# C210_0002_NORA_Module_220601.net
KiCad netlist of a schematic drawn in Altium Designer
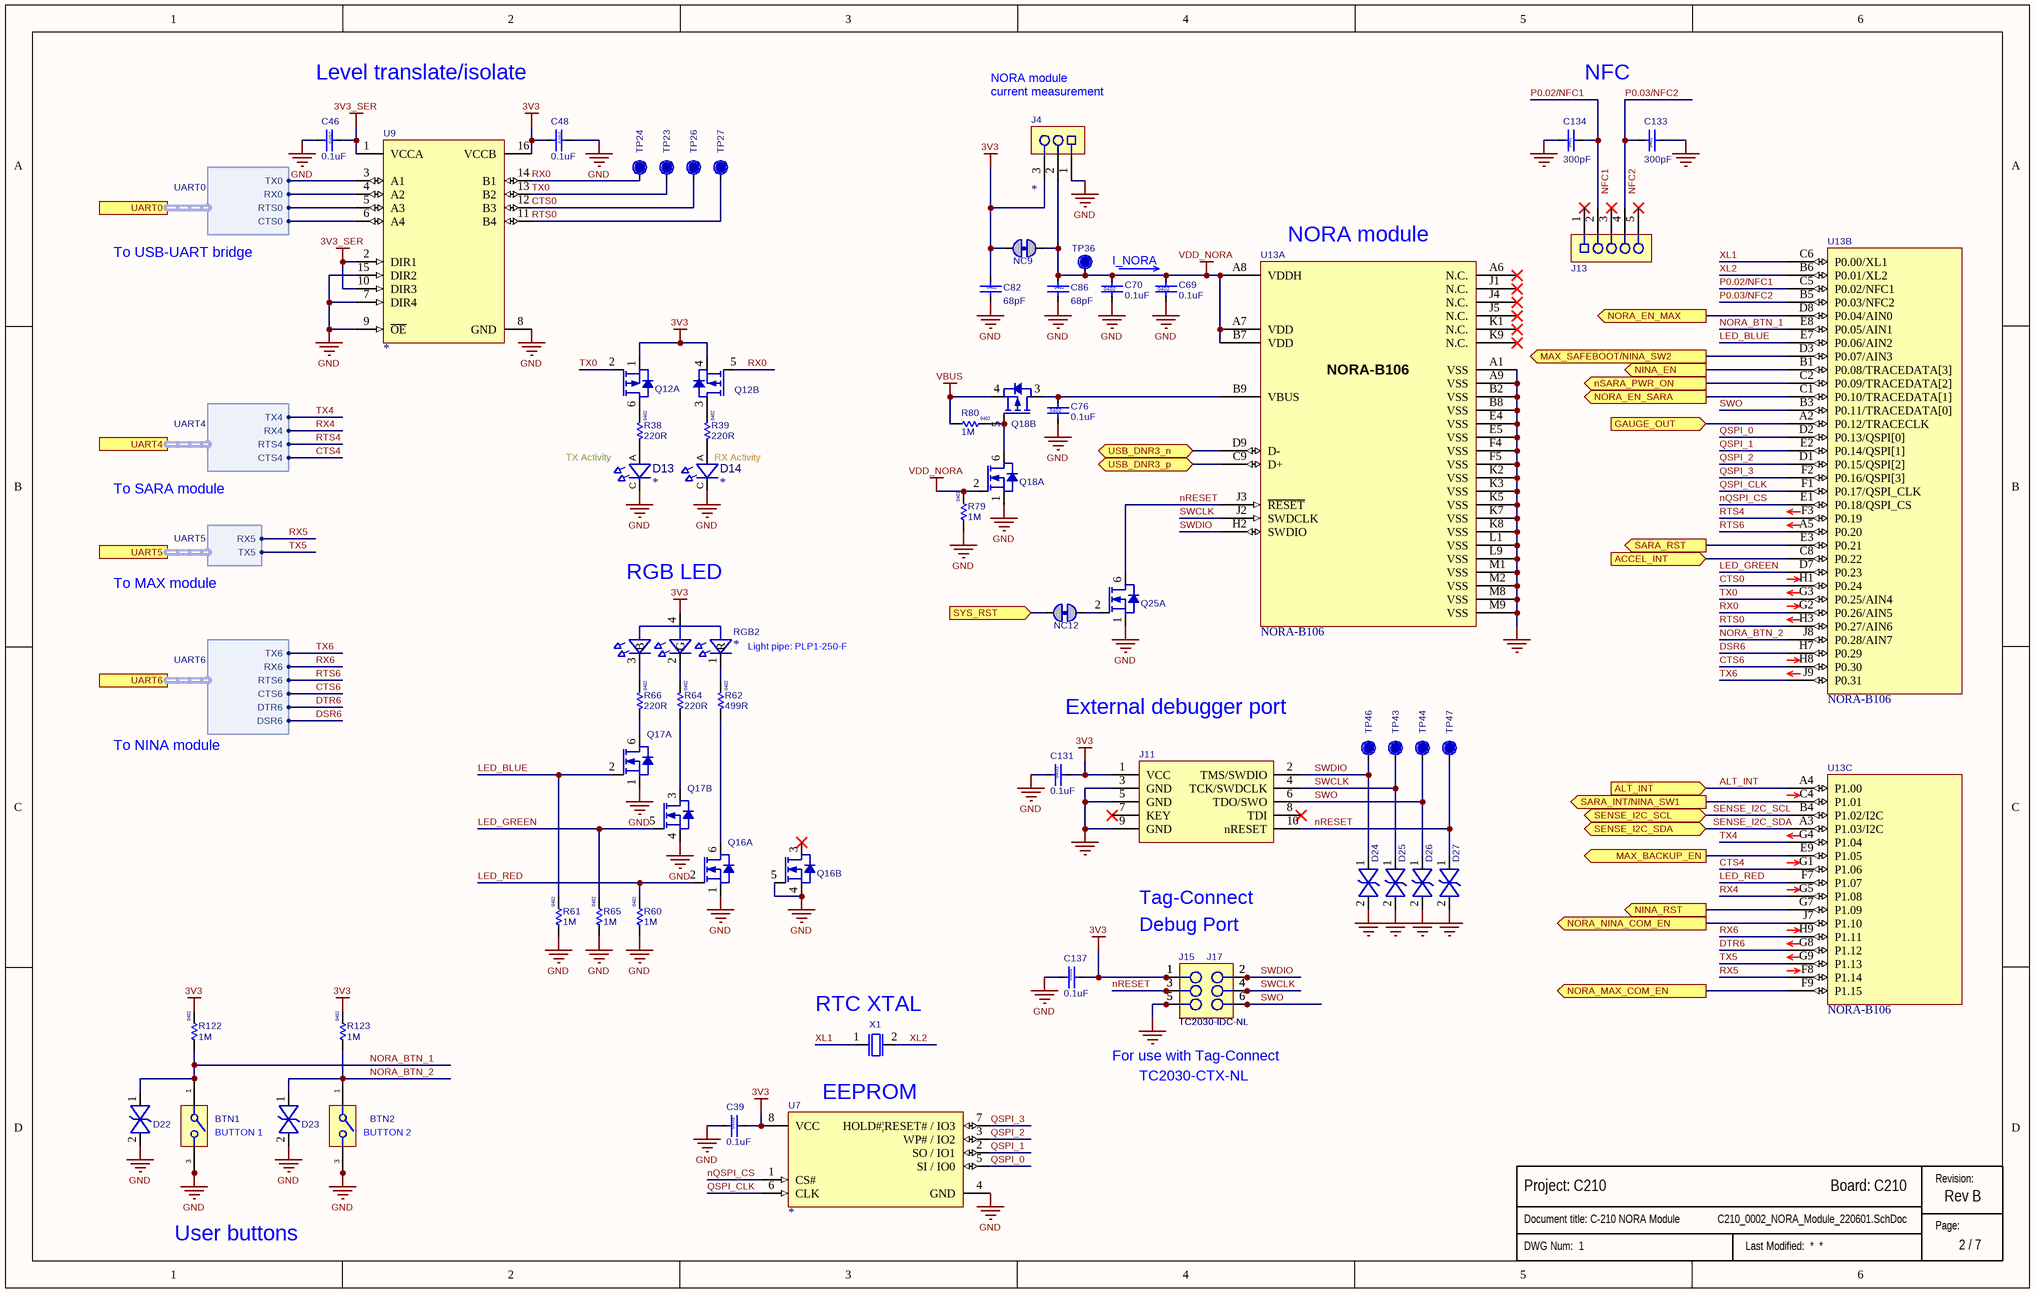
[diagram p0: C210_0002_NORA_Module_220601.SchDoc]

(export (version "E")
  (design (tool "Eeschema 10.0.6"))
  (components
    (comp (ref "BTN1")
      (value "TL6120DF300QG")
      (footprint "TL6120DF300QG")
      (description "Button, Tactile, SPST, NO, SMT, Vert")
      (fields (field (name "VOLTAGE") "None"))
      (libsource (lib "TL6120DF300QG") (part "TL6120DF300QG"))
    )
    (comp (ref "BTN2")
      (value "TL6120DF300QG")
      (footprint "TL6120DF300QG")
      (description "Button, Tactile, SPST, NO, SMT, Vert")
      (fields (field (name "VOLTAGE") "None"))
      (libsource (lib "TL6120DF300QG") (part "TL6120DF300QG"))
    )
    (comp (ref "C39")
      (value "0.1uF")
      (footprint "Cap 0402 HD")
      (description "Cap, Ceramic 0.1uF 10V 10% X5R 0402")
      (fields
        (field (name "SIZE") "0402")
        (field (name "PART NUMBER") "120-00016")
        (field (name "MANUFACTURER") "Murata Electronics North America")
      )
      (libsource (lib "Arena_Parts_DB_Lib") (part "Cap Chip"))
    )
    (comp (ref "C46")
      (value "0.1uF")
      (footprint "Cap 0402 HD")
      (description "Cap, Ceramic 0.1uF 10V 10% X5R 0402")
      (fields
        (field (name "SIZE") "0402")
        (field (name "PART NUMBER") "120-00016")
        (field (name "MANUFACTURER") "Murata Electronics North America")
      )
      (libsource (lib "Arena_Parts_DB_Lib") (part "Cap Chip"))
    )
    (comp (ref "C48")
      (value "0.1uF")
      (footprint "Cap 0402 HD")
      (description "Cap, Ceramic 0.1uF 10V 10% X5R 0402")
      (fields
        (field (name "SIZE") "0402")
        (field (name "PART NUMBER") "120-00016")
        (field (name "MANUFACTURER") "Murata Electronics North America")
      )
      (libsource (lib "Arena_Parts_DB_Lib") (part "Cap Chip"))
    )
    (comp (ref "C69")
      (value "0.1uF")
      (footprint "Cap 0402 HD")
      (description "Cap, Ceramic 0.1uF 10V 10% X5R 0402")
      (fields
        (field (name "SIZE") "0402")
        (field (name "PART NUMBER") "120-00016")
        (field (name "MANUFACTURER") "Murata Electronics North America")
      )
      (libsource (lib "Arena_Parts_DB_Lib") (part "Cap Chip"))
    )
    (comp (ref "C70")
      (value "0.1uF")
      (footprint "Cap 0402 HD")
      (description "Cap, Ceramic 0.1uF 10V 10% X5R 0402")
      (fields
        (field (name "SIZE") "0402")
        (field (name "PART NUMBER") "120-00016")
        (field (name "MANUFACTURER") "Murata Electronics North America")
      )
      (libsource (lib "Arena_Parts_DB_Lib") (part "Cap Chip"))
    )
    (comp (ref "C76")
      (value "0.1uF")
      (footprint "Cap 0402 HD")
      (description "Cap, Ceramic 0.1uF 10V 10% X5R 0402")
      (fields
        (field (name "SIZE") "0402")
        (field (name "PART NUMBER") "120-00016")
        (field (name "MANUFACTURER") "Murata Electronics North America")
      )
      (libsource (lib "Arena_Parts_DB_Lib") (part "Cap Chip"))
    )
    (comp (ref "C82")
      (value "68pF")
      (footprint "Cap 0402 HD")
      (description "Cap, Ceramic, 68pF, 50V, 1%, NP0, 0402")
      (fields
        (field (name "SIZE") "0402")
        (field (name "PART NUMBER") "120-00047")
        (field (name "TOLERANCE") "+/- 1%")
      )
      (libsource (lib "Arena_Parts_DB_Lib") (part "Cap Chip"))
    )
    (comp (ref "C86")
      (value "68pF")
      (footprint "Cap 0402 HD")
      (description "Cap, Ceramic, 68pF, 50V, 1%, NP0, 0402")
      (fields
        (field (name "SIZE") "0402")
        (field (name "PART NUMBER") "120-00047")
        (field (name "TOLERANCE") "+/- 1%")
      )
      (libsource (lib "Arena_Parts_DB_Lib") (part "Cap Chip"))
    )
    (comp (ref "C131")
      (value "0.1uF")
      (footprint "Cap 0402 HD")
      (description "Cap, Ceramic 0.1uF 10V 10% X5R 0402")
      (fields
        (field (name "SIZE") "0402")
        (field (name "PART NUMBER") "120-00016")
        (field (name "MANUFACTURER") "Murata Electronics North America")
      )
      (libsource (lib "Arena_Parts_DB_Lib") (part "Cap Chip"))
    )
    (comp (ref "C133")
      (value "300pF")
      (footprint "Cap 0402 HD")
      (description "Cap, Ceramic 300pF 50V 5% NP0 0402")
      (fields
        (field (name "SIZE") "0402")
        (field (name "PART NUMBER") "120-00099")
        (field (name "MANUFACTURER") "Murata Electronics North America")
      )
      (libsource (lib "Arena_Parts_DB_Lib") (part "Cap Chip"))
    )
    (comp (ref "C134")
      (value "300pF")
      (footprint "Cap 0402 HD")
      (description "Cap, Ceramic 300pF 50V 5% NP0 0402")
      (fields
        (field (name "SIZE") "0402")
        (field (name "PART NUMBER") "120-00099")
        (field (name "MANUFACTURER") "Murata Electronics North America")
      )
      (libsource (lib "Arena_Parts_DB_Lib") (part "Cap Chip"))
    )
    (comp (ref "C137")
      (value "0.1uF")
      (footprint "Cap 0402 HD")
      (description "Cap, Ceramic 0.1uF 10V 10% X5R 0402")
      (fields
        (field (name "SIZE") "0402")
        (field (name "PART NUMBER") "120-00016")
        (field (name "MANUFACTURER") "Murata Electronics North America")
      )
      (libsource (lib "Arena_Parts_DB_Lib") (part "Cap Chip"))
    )
    (comp (ref "D13")
      (value "115-00019")
      (footprint "LTST-C190KGKT")
      (description "DIODE, LED, SMT, GREEN, CLEAR LENS, 2.0V 20mA, 0603")
      (fields (field (name "VOLTAGE") "2.0V") (field (name "COLOR") "*"))
      (libsource (lib "LTST-C190KGKT") (part "LTST-C190KGKT"))
    )
    (comp (ref "D14")
      (value "LTST-C190YKT")
      (footprint "LTST-C190YKT")
      (description "DIODE, LED, SMT, YELLOW, CLEAR LENS, 2.1V 10mA, 0603")
      (fields (field (name "VOLTAGE") "2.1V") (field (name "COLOR") "*"))
      (libsource (lib "LTST-C190YKT") (part "LTST-C190YKT"))
    )
    (comp (ref "D22")
      (value "110-00041")
      (footprint "SOD-523_ALT")
      (description "Diode TVS 5VWM BiDIR SOD523")
      (fields (field (name "VOLTAGE") "5VWM"))
      (libsource (lib "Arena_Parts_DB_Lib") (part "Diode_TVS"))
    )
    (comp (ref "D23")
      (value "110-00041")
      (footprint "SOD-523_ALT")
      (description "Diode TVS 5VWM BiDIR SOD523")
      (fields (field (name "VOLTAGE") "5VWM"))
      (libsource (lib "Arena_Parts_DB_Lib") (part "Diode_TVS"))
    )
    (comp (ref "D24")
      (value "110-00041")
      (footprint "SOD-523_ALT")
      (description "Diode TVS 5VWM BiDIR SOD523")
      (fields (field (name "VOLTAGE") "5VWM"))
      (libsource (lib "Arena_Parts_DB_Lib") (part "Diode_TVS"))
    )
    (comp (ref "D25")
      (value "110-00041")
      (footprint "SOD-523_ALT")
      (description "Diode TVS 5VWM BiDIR SOD523")
      (fields (field (name "VOLTAGE") "5VWM"))
      (libsource (lib "Arena_Parts_DB_Lib") (part "Diode_TVS"))
    )
    (comp (ref "D26")
      (value "110-00041")
      (footprint "SOD-523_ALT")
      (description "Diode TVS 5VWM BiDIR SOD523")
      (fields (field (name "VOLTAGE") "5VWM"))
      (libsource (lib "Arena_Parts_DB_Lib") (part "Diode_TVS"))
    )
    (comp (ref "D27")
      (value "110-00041")
      (footprint "SOD-523_ALT")
      (description "Diode TVS 5VWM BiDIR SOD523")
      (fields (field (name "VOLTAGE") "5VWM"))
      (libsource (lib "Arena_Parts_DB_Lib") (part "Diode_TVS"))
    )
    (comp (ref "J4")
      (value "130-00105")
      (footprint "HDR-0.1P-3Pin-1Row-SMT")
      (description "Header, 0.100\" Pitch, 3 Pin, Vertical SMT, Black")
      (fields (field (name "MANUFACTURER P/N") "*") (field (name "VOLTAGE") "None"))
      (libsource (lib "Arena_Parts_DB_Lib") (part "CON-3Pin_1Row"))
    )
    (comp (ref "J11")
      (value "FTSH-105-01-F-DH-A-C - JTAG")
      (footprint "FTSH-105-01-F-DH-A-C")
      (description "Header 0.05\" 10Pin 2Row SMD, RA, Black")
      (fields (field (name "MANUFACTURER") "Samtec"))
      (libsource (lib "FTSH-105-01-F-DH-A-C") (part "FTSH-105-01-F-DH-A-C - JTAG"))
    )
    (comp (ref "J13")
      (value "130-00098")
      (footprint "Molex 051281-0594")
      (description "CON FFC/FPC 0.50mm 5Pos R/A")
      (fields (field (name "MANUFACTURER") "Molex Inc") (field (name "VOLTAGE") "50V"))
      (libsource (lib "Arena_Parts_DB_Lib") (part "CON-5Pin_1Row"))
    )
    (comp (ref "J15")
      (value "TC2030-IDC-NLDNP")
      (footprint "TC2030-IDC-NL")
      (description "CON PADS FOR CBL PLUG-OF-NAILS 6-PIN NO LEGS")
      (fields
        (field (name "PART NUMBER") "TC2030-IDC-NL")
        (field (name "MANUFACTURER") "TAG Connect")
        (field (name "MANUFACTURER P/N") "TC2030-IDC-NL")
        (field (name "ADDED BY") "emoo")
      )
      (libsource (lib "PCB_Misc") (part "CON-6Pin_2Row_ALT"))
    )
    (comp (ref "J17")
      (value "TC2030-IDC-NLDNP")
      (footprint "TC2030-IDC-NL No Hole")
      (description "CON PADS FOR CBL PLUG-OF-NAILS 6-PIN NO LEGS")
      (fields
        (field (name "PART NUMBER") "TC2030-IDC-NL")
        (field (name "MANUFACTURER") "TAG Connect")
        (field (name "MANUFACTURER P/N") "TC2030-IDC-NL")
        (field (name "ADDED BY") "emoo")
      )
      (libsource (lib "PCB_Misc") (part "CON-6Pin_2Row_ALT"))
    )
    (comp (ref "NC9")
      (value "Solderbridge-ShortDNP")
      (footprint "Solderbridge-Short")
      (description "Solderbridge-Short")
      (fields (field (name "ADDED BY") "Paul B"))
      (libsource (lib "PCB_Misc") (part "Solderbridge-Short"))
    )
    (comp (ref "NC12")
      (value "Solderbridge-ShortDNP")
      (footprint "Solderbridge-Short")
      (description "Solderbridge-Short")
      (fields (field (name "ADDED BY") "Paul B"))
      (libsource (lib "PCB_Misc") (part "Solderbridge-Short"))
    )
    (comp (ref "Q12")
      (value "FDY2000PZ")
      (footprint "FDY2000PZ")
      (description "MOSFET DUAL P-CH 20V SOT-563, -350mA")
      (fields (field (name "VOLTAGE") "20V"))
      (libsource (lib "FDY2000PZ") (part "MOSFET-Dual-P_Chan"))
    )
    (comp (ref "Q16")
      (value "140-00016")
      (footprint "SOT-563")
      (description "MOSFET 2N-CH 20V 0.8A, SOT-563")
      (fields (field (name "VOLTAGE") "20V"))
      (libsource (lib "Arena_Parts_DB_Lib") (part "MOSFET-N-Dual"))
    )
    (comp (ref "Q17")
      (value "140-00016")
      (footprint "SOT-563")
      (description "MOSFET 2N-CH 20V 0.8A, SOT-563")
      (fields (field (name "VOLTAGE") "20V"))
      (libsource (lib "Arena_Parts_DB_Lib") (part "MOSFET-N-Dual"))
    )
    (comp (ref "Q18")
      (value "140-00030")
      (footprint "SOT-563")
      (description "MOSFET N/P-CH 20V SOT-563, 540 mA, −430 mA")
      (fields (field (name "VOLTAGE") "20V"))
      (libsource (lib "Arena_Parts_DB_Lib") (part "MOSFET-N-P_Pair"))
    )
    (comp (ref "Q25")
      (value "140-00016")
      (footprint "SOT-563")
      (description "MOSFET 2N-CH 20V 0.8A, SOT-563")
      (fields (field (name "VOLTAGE") "20V"))
      (libsource (lib "Arena_Parts_DB_Lib") (part "MOSFET-N-Dual"))
    )
    (comp (ref "R38")
      (value "220R")
      (footprint "RES 0402 HD")
      (description "Resistor, 220ohm, 5%, 1/16W, 0402.")
      (fields
        (field (name "SIZE") "0402")
        (field (name "PART NUMBER") "180-00098")
        (field (name "MANUFACTURER") "Panasonic Electronic Components")
      )
      (libsource (lib "Arena_Parts_DB_Lib") (part "Res sm"))
    )
    (comp (ref "R39")
      (value "220R")
      (footprint "RES 0402 HD")
      (description "Resistor, 220ohm, 5%, 1/16W, 0402.")
      (fields
        (field (name "SIZE") "0402")
        (field (name "PART NUMBER") "180-00098")
        (field (name "MANUFACTURER") "Panasonic Electronic Components")
      )
      (libsource (lib "Arena_Parts_DB_Lib") (part "Res sm"))
    )
    (comp (ref "R60")
      (value "1M")
      (footprint "RES 0402 HD")
      (description "Resistor 1M ohm 1%, 1/16W, 0402")
      (fields
        (field (name "SIZE") "0402")
        (field (name "PART NUMBER") "180-00054")
        (field (name "POWER") "1/16W")
      )
      (libsource (lib "Arena_Parts_DB_Lib") (part "Res sm"))
    )
    (comp (ref "R61")
      (value "1M")
      (footprint "RES 0402 HD")
      (description "Resistor 1M ohm 1%, 1/16W, 0402")
      (fields
        (field (name "SIZE") "0402")
        (field (name "PART NUMBER") "180-00054")
        (field (name "POWER") "1/16W")
      )
      (libsource (lib "Arena_Parts_DB_Lib") (part "Res sm"))
    )
    (comp (ref "R62")
      (value "499R")
      (footprint "RES 0402 HD")
      (description "Resistor, 499ohm, 1%, 1/16W, 0402")
      (fields
        (field (name "SIZE") "0402")
        (field (name "PART NUMBER") "180-00031")
        (field (name "MANUFACTURER") "Rohm Semiconductor")
      )
      (libsource (lib "Arena_Parts_DB_Lib") (part "Res sm"))
    )
    (comp (ref "R64")
      (value "220R")
      (footprint "RES 0402 HD")
      (description "Resistor, 220ohm, 5%, 1/16W, 0402.")
      (fields
        (field (name "SIZE") "0402")
        (field (name "PART NUMBER") "180-00098")
        (field (name "MANUFACTURER") "Panasonic Electronic Components")
      )
      (libsource (lib "Arena_Parts_DB_Lib") (part "Res sm"))
    )
    (comp (ref "R65")
      (value "1M")
      (footprint "RES 0402 HD")
      (description "Resistor 1M ohm 1%, 1/16W, 0402")
      (fields
        (field (name "SIZE") "0402")
        (field (name "PART NUMBER") "180-00054")
        (field (name "POWER") "1/16W")
      )
      (libsource (lib "Arena_Parts_DB_Lib") (part "Res sm"))
    )
    (comp (ref "R66")
      (value "220R")
      (footprint "RES 0402 HD")
      (description "Resistor, 220ohm, 5%, 1/16W, 0402.")
      (fields
        (field (name "SIZE") "0402")
        (field (name "PART NUMBER") "180-00098")
        (field (name "MANUFACTURER") "Panasonic Electronic Components")
      )
      (libsource (lib "Arena_Parts_DB_Lib") (part "Res sm"))
    )
    (comp (ref "R79")
      (value "1M")
      (footprint "RES 0402 HD")
      (description "Resistor 1M ohm 1%, 1/16W, 0402")
      (fields
        (field (name "SIZE") "0402")
        (field (name "PART NUMBER") "180-00054")
        (field (name "POWER") "1/16W")
      )
      (libsource (lib "Arena_Parts_DB_Lib") (part "Res sm"))
    )
    (comp (ref "R80")
      (value "1M")
      (footprint "RES 0402 HD")
      (description "Resistor 1M ohm 1%, 1/16W, 0402")
      (fields
        (field (name "SIZE") "0402")
        (field (name "PART NUMBER") "180-00054")
        (field (name "POWER") "1/16W")
      )
      (libsource (lib "Arena_Parts_DB_Lib") (part "Res sm"))
    )
    (comp (ref "R122")
      (value "1M")
      (footprint "RES 0402 HD")
      (description "Resistor 1M ohm 1%, 1/16W, 0402")
      (fields
        (field (name "SIZE") "0402")
        (field (name "PART NUMBER") "180-00054")
        (field (name "POWER") "1/16W")
      )
      (libsource (lib "Arena_Parts_DB_Lib") (part "Res sm"))
    )
    (comp (ref "R123")
      (value "1M")
      (footprint "RES 0402 HD")
      (description "Resistor 1M ohm 1%, 1/16W, 0402")
      (fields
        (field (name "SIZE") "0402")
        (field (name "PART NUMBER") "180-00054")
        (field (name "POWER") "1/16W")
      )
      (libsource (lib "Arena_Parts_DB_Lib") (part "Res sm"))
    )
    (comp (ref "RGB2")
      (value "115-00026")
      (footprint "LED_1616")
      (description "LED RGB SMT 0606")
      (fields (field (name "COLOR") "*") (field (name "VOLTAGE") "None"))
      (libsource (lib "Arena_Parts_DB_Lib") (part "LED_RGB_CA_4"))
    )
    (comp (ref "TP23")
      (value "TP")
      (footprint "TP12R")
      (description "Testpoint, Round 1.0mm Dia")
      (fields
        (field (name "PART NUMBER") "TP10R")
        (field (name "ADDED BY") "Jeremy D")
        (field (name "CHECKED BY") "Paul B")
      )
      (libsource (lib "PCB_Misc") (part "TP_R"))
    )
    (comp (ref "TP24")
      (value "TP")
      (footprint "TP12R")
      (description "Testpoint, Round 1.0mm Dia")
      (fields
        (field (name "PART NUMBER") "TP10R")
        (field (name "ADDED BY") "Jeremy D")
        (field (name "CHECKED BY") "Paul B")
      )
      (libsource (lib "PCB_Misc") (part "TP_R"))
    )
    (comp (ref "TP26")
      (value "TP")
      (footprint "TP12R")
      (description "Testpoint, Round 1.0mm Dia")
      (fields
        (field (name "PART NUMBER") "TP10R")
        (field (name "ADDED BY") "Jeremy D")
        (field (name "CHECKED BY") "Paul B")
      )
      (libsource (lib "PCB_Misc") (part "TP_R"))
    )
    (comp (ref "TP27")
      (value "TP")
      (footprint "TP12R")
      (description "Testpoint, Round 1.0mm Dia")
      (fields
        (field (name "PART NUMBER") "TP10R")
        (field (name "ADDED BY") "Jeremy D")
        (field (name "CHECKED BY") "Paul B")
      )
      (libsource (lib "PCB_Misc") (part "TP_R"))
    )
    (comp (ref "TP36")
      (value "TP")
      (footprint "TP12R")
      (description "Testpoint, Round 1.0mm Dia")
      (fields
        (field (name "PART NUMBER") "TP10R")
        (field (name "ADDED BY") "Jeremy D")
        (field (name "CHECKED BY") "Paul B")
      )
      (libsource (lib "PCB_Misc") (part "TP_R"))
    )
    (comp (ref "TP43")
      (value "TP")
      (footprint "TP12R")
      (description "Testpoint, Round 1.0mm Dia")
      (fields
        (field (name "PART NUMBER") "TP10R")
        (field (name "ADDED BY") "Jeremy D")
        (field (name "CHECKED BY") "Paul B")
      )
      (libsource (lib "PCB_Misc") (part "TP_R"))
    )
    (comp (ref "TP44")
      (value "TP")
      (footprint "TP12R")
      (description "Testpoint, Round 1.0mm Dia")
      (fields
        (field (name "PART NUMBER") "TP10R")
        (field (name "ADDED BY") "Jeremy D")
        (field (name "CHECKED BY") "Paul B")
      )
      (libsource (lib "PCB_Misc") (part "TP_R"))
    )
    (comp (ref "TP46")
      (value "TP")
      (footprint "TP12R")
      (description "Testpoint, Round 1.0mm Dia")
      (fields
        (field (name "PART NUMBER") "TP10R")
        (field (name "ADDED BY") "Jeremy D")
        (field (name "CHECKED BY") "Paul B")
      )
      (libsource (lib "PCB_Misc") (part "TP_R"))
    )
    (comp (ref "TP47")
      (value "TP")
      (footprint "TP12R")
      (description "Testpoint, Round 1.0mm Dia")
      (fields
        (field (name "PART NUMBER") "TP10R")
        (field (name "ADDED BY") "Jeremy D")
        (field (name "CHECKED BY") "Paul B")
      )
      (libsource (lib "PCB_Misc") (part "TP_R"))
    )
    (comp (ref "U7")
      (value "240-00033")
      (footprint "WSON1.27P-8Pin_W-Pad")
      (description "64Mbit QSPI NOR Flash")
      (fields (field (name "MANUFACTURER P/N") "*") (field (name "VOLTAGE") "3.6V"))
      (libsource (lib "Arena_Parts_DB_Lib") (part "SPI_Flash_Memory_8Pin"))
    )
    (comp (ref "U9")
      (value "225-00011")
      (footprint "QFN0.5P2x6-16Pin_W-Pad")
      (description "Voltage Level Translator Bidirectional 1 Circuit 4 Channel 380Mbps 16-DHVQFN (2.5x3.5)")
      (fields (field (name "MANUFACTURER P/N") "*") (field (name "VOLTAGE") "3.6V"))
      (libsource (lib "Arena_Parts_DB_Lib") (part "74AVC4TD245"))
    )
    (comp (ref "U13")
      (value "NORA-B106")
      (footprint "NORA_LGA82R_1430X1040X180_ANT")
      (description "u-blox NORA-B106 Bluetooth 5.2 LE module - dual core")
      (fields (field (name "MANUFACTURER") "u-blox"))
      (libsource (lib "ubloxLib") (part "NORA-B106"))
    )
    (comp (ref "X1")
      (value "100-00005")
      (footprint "XTAL_3215")
      (description "XTAL, 2Pin, 32.768kHz, 7pF 20ppm")
      (fields (field (name "MANUFACTURER") "Epson"))
      (libsource (lib "Arena_Parts_DB_Lib") (part "XTAL_2Pin"))
    )
  )
  (nets
    (net (code "5") (name "/ACCEL_INT") (class "Default")
      (node (ref "U13") (pin "C8") (pinfunction "P0.22_C8") (pintype "bidirectional"))
    )
    (net (code "6") (name "/ALT_INT") (class "Default")
      (node (ref "U13") (pin "A4") (pinfunction "P1.00_A4") (pintype "bidirectional"))
    )
    (net (code "7") (name "/CTS0") (class "Default")
      (node (ref "TP26") (pin "1") (pintype "passive"))
      (node (ref "U13") (pin "H1") (pinfunction "P0.24_H1") (pintype "bidirectional"))
      (node (ref "U9") (pin "12") (pinfunction "B3_12") (pintype "bidirectional"))
    )
    (net (code "8") (name "/CTS4") (class "Default")
      (node (ref "U13") (pin "G1") (pinfunction "P1.06_G1") (pintype "bidirectional"))
    )
    (net (code "9") (name "/CTS6") (class "Default")
      (node (ref "U13") (pin "H8") (pinfunction "P0.30_H8") (pintype "bidirectional"))
    )
    (net (code "10") (name "/DSR6") (class "Default")
      (node (ref "U13") (pin "H7") (pinfunction "P0.29_H7") (pintype "bidirectional"))
    )
    (net (code "11") (name "/DTR6") (class "Default")
      (node (ref "U13") (pin "G8") (pinfunction "P1.12_G8") (pintype "bidirectional"))
    )
    (net (code "12") (name "/GAUGE_OUT") (class "Default")
      (node (ref "U13") (pin "A2") (pinfunction "P0.12/TRACECLK_A2") (pintype "bidirectional"))
    )
    (net (code "13") (name "/LED_BLUE") (class "Default")
      (node (ref "Q17") (pin "2") (pinfunction "G1_2") (pintype "passive"))
      (node (ref "R61") (pin "2") (pinfunction "2_2") (pintype "passive"))
      (node (ref "U13") (pin "E7") (pinfunction "P0.06/AIN2_E7") (pintype "bidirectional"))
    )
    (net (code "14") (name "/LED_GREEN") (class "Default")
      (node (ref "Q17") (pin "5") (pinfunction "G2_5") (pintype "passive"))
      (node (ref "R65") (pin "2") (pinfunction "2_2") (pintype "passive"))
      (node (ref "U13") (pin "D7") (pinfunction "P0.23_D7") (pintype "bidirectional"))
    )
    (net (code "15") (name "/LED_RED") (class "Default")
      (node (ref "Q16") (pin "2") (pinfunction "G1_2") (pintype "passive"))
      (node (ref "R60") (pin "2") (pinfunction "2_2") (pintype "passive"))
      (node (ref "U13") (pin "F7") (pinfunction "P1.07_F7") (pintype "bidirectional"))
    )
    (net (code "16") (name "/MAX_BACKUP_EN") (class "Default")
      (node (ref "U13") (pin "E9") (pinfunction "P1.05_E9") (pintype "bidirectional"))
    )
    (net (code "17") (name "/MAX_SAFEBOOT{slash}NINA_SW2") (class "Default")
      (node (ref "U13") (pin "D3") (pinfunction "P0.07/AIN3_D3") (pintype "bidirectional"))
    )
    (net (code "18") (name "/NFC1") (class "Default")
      (node (ref "C134") (pin "2") (pinfunction "2_2") (pintype "passive"))
      (node (ref "J13") (pin "2") (pinfunction "2_2") (pintype "passive"))
      (node (ref "U13") (pin "C5") (pinfunction "P0.02/NFC1_C5") (pintype "bidirectional"))
    )
    (net (code "19") (name "/NFC2") (class "Default")
      (node (ref "C133") (pin "1") (pinfunction "1_1") (pintype "passive"))
      (node (ref "J13") (pin "4") (pinfunction "4_4") (pintype "passive"))
      (node (ref "U13") (pin "B5") (pinfunction "P0.03/NFC2_B5") (pintype "bidirectional"))
    )
    (net (code "20") (name "/NINA_EN") (class "Default")
      (node (ref "U13") (pin "B1") (pinfunction "P0.08/TRACEDATA[3]_B1") (pintype "bidirectional"))
    )
    (net (code "21") (name "/NINA_RST") (class "Default")
      (node (ref "U13") (pin "G7") (pinfunction "P1.09_G7") (pintype "bidirectional"))
    )
    (net (code "22") (name "/NORA_BTN_1") (class "Default")
      (node (ref "BTN1") (pin "1") (pinfunction "1_1") (pintype "passive"))
      (node (ref "BTN1") (pin "2") (pinfunction "2_2") (pintype "passive"))
      (node (ref "D22") (pin "1") (pintype "passive"))
      (node (ref "R122") (pin "1") (pinfunction "1_1") (pintype "passive"))
      (node (ref "U13") (pin "E8") (pinfunction "P0.05/AIN1_E8") (pintype "bidirectional"))
    )
    (net (code "23") (name "/NORA_BTN_2") (class "Default")
      (node (ref "BTN2") (pin "1") (pinfunction "1_1") (pintype "passive"))
      (node (ref "BTN2") (pin "2") (pinfunction "2_2") (pintype "passive"))
      (node (ref "D23") (pin "1") (pintype "passive"))
      (node (ref "R123") (pin "1") (pinfunction "1_1") (pintype "passive"))
      (node (ref "U13") (pin "J8") (pinfunction "P0.28/AIN7_J8") (pintype "bidirectional"))
    )
    (net (code "24") (name "/NORA_EN_MAX") (class "Default")
      (node (ref "U13") (pin "D8") (pinfunction "P0.04/AIN0_D8") (pintype "bidirectional"))
    )
    (net (code "25") (name "/NORA_EN_SARA") (class "Default")
      (node (ref "U13") (pin "C1") (pinfunction "P0.10/TRACEDATA[1]_C1") (pintype "bidirectional"))
    )
    (net (code "26") (name "/NORA_MAX_COM_EN") (class "Default")
      (node (ref "U13") (pin "F9") (pinfunction "P1.15_F9") (pintype "bidirectional"))
    )
    (net (code "27") (name "/NORA_NINA_COM_EN") (class "Default")
      (node (ref "U13") (pin "J7") (pinfunction "P1.10_J7") (pintype "bidirectional"))
    )
    (net (code "28") (name "/QSPI_0") (class "Default")
      (node (ref "U13") (pin "D2") (pinfunction "P0.13/QSPI[0]_D2") (pintype "bidirectional"))
      (node (ref "U7") (pin "5") (pinfunction "SI_/_IO0_5") (pintype "bidirectional"))
    )
    (net (code "29") (name "/QSPI_1") (class "Default")
      (node (ref "U13") (pin "E2") (pinfunction "P0.14/QSPI[1]_E2") (pintype "bidirectional"))
      (node (ref "U7") (pin "2") (pinfunction "SO_/_IO1_2") (pintype "bidirectional"))
    )
    (net (code "30") (name "/QSPI_2") (class "Default")
      (node (ref "U13") (pin "D1") (pinfunction "P0.15/QSPI[2]_D1") (pintype "bidirectional"))
      (node (ref "U7") (pin "3") (pinfunction "WP#_/_IO2_3") (pintype "bidirectional"))
    )
    (net (code "31") (name "/QSPI_3") (class "Default")
      (node (ref "U13") (pin "F2") (pinfunction "P0.16/QSPI[3]_F2") (pintype "bidirectional"))
      (node (ref "U7") (pin "7") (pinfunction "HOLD#¦RESET#_/_IO3_7") (pintype "bidirectional"))
    )
    (net (code "32") (name "/QSPI_CLK") (class "Default")
      (node (ref "U13") (pin "F1") (pinfunction "P0.17/QSPI_CLK_F1") (pintype "bidirectional"))
      (node (ref "U7") (pin "6") (pinfunction "CLK_6") (pintype "input"))
    )
    (net (code "33") (name "/RTS0") (class "Default")
      (node (ref "TP27") (pin "1") (pintype "passive"))
      (node (ref "U13") (pin "H3") (pinfunction "P0.27/AIN6_H3") (pintype "bidirectional"))
      (node (ref "U9") (pin "11") (pinfunction "B4_11") (pintype "bidirectional"))
    )
    (net (code "34") (name "/RTS4") (class "Default")
      (node (ref "U13") (pin "F3") (pinfunction "P0.19_F3") (pintype "bidirectional"))
    )
    (net (code "35") (name "/RTS6") (class "Default")
      (node (ref "U13") (pin "A5") (pinfunction "P0.20_A5") (pintype "bidirectional"))
    )
    (net (code "36") (name "/RX0") (class "Default")
      (node (ref "Q12") (pin "5") (pinfunction "G2_5") (pintype "passive"))
      (node (ref "TP24") (pin "1") (pintype "passive"))
      (node (ref "U13") (pin "G2") (pinfunction "P0.26/AIN5_G2") (pintype "bidirectional"))
      (node (ref "U9") (pin "14") (pinfunction "B1_14") (pintype "bidirectional"))
    )
    (net (code "37") (name "/RX4") (class "Default")
      (node (ref "U13") (pin "G5") (pinfunction "P1.08_G5") (pintype "bidirectional"))
    )
    (net (code "38") (name "/RX5") (class "Default")
      (node (ref "U13") (pin "F8") (pinfunction "P1.14_F8") (pintype "bidirectional"))
    )
    (net (code "39") (name "/RX6") (class "Default")
      (node (ref "U13") (pin "H9") (pinfunction "P1.11_H9") (pintype "bidirectional"))
    )
    (net (code "40") (name "/SARA_INT{slash}NINA_SW1") (class "Default")
      (node (ref "U13") (pin "C4") (pinfunction "P1.01_C4") (pintype "bidirectional"))
    )
    (net (code "41") (name "/SARA_RST") (class "Default")
      (node (ref "U13") (pin "E3") (pinfunction "P0.21_E3") (pintype "bidirectional"))
    )
    (net (code "42") (name "/SENSE_I2C_SCL") (class "Default")
      (node (ref "U13") (pin "B4") (pinfunction "P1.02/I2C_B4") (pintype "bidirectional"))
    )
    (net (code "43") (name "/SENSE_I2C_SDA") (class "Default")
      (node (ref "U13") (pin "A3") (pinfunction "P1.03/I2C_A3") (pintype "bidirectional"))
    )
    (net (code "44") (name "/SWCLK") (class "Default")
      (node (ref "D25") (pin "1") (pintype "passive"))
      (node (ref "J11") (pin "4") (pinfunction "TCK/SWDCLK_4") (pintype "passive"))
      (node (ref "J15") (pin "4") (pintype "passive"))
      (node (ref "J17") (pin "4") (pintype "passive"))
      (node (ref "TP43") (pin "1") (pintype "passive"))
      (node (ref "U13") (pin "J2") (pinfunction "SWDCLK_J2") (pintype "input"))
    )
    (net (code "45") (name "/SWDIO") (class "Default")
      (node (ref "D24") (pin "1") (pintype "passive"))
      (node (ref "J11") (pin "2") (pinfunction "TMS/SWDIO_2") (pintype "passive"))
      (node (ref "J15") (pin "2") (pintype "passive"))
      (node (ref "J17") (pin "2") (pintype "passive"))
      (node (ref "TP46") (pin "1") (pintype "passive"))
      (node (ref "U13") (pin "H2") (pinfunction "SWDIO_H2") (pintype "bidirectional"))
    )
    (net (code "46") (name "/SWO") (class "Default")
      (node (ref "D26") (pin "1") (pintype "passive"))
      (node (ref "J11") (pin "6") (pinfunction "TDO/SWO_6") (pintype "passive"))
      (node (ref "J15") (pin "6") (pintype "passive"))
      (node (ref "J17") (pin "6") (pintype "passive"))
      (node (ref "TP44") (pin "1") (pintype "passive"))
      (node (ref "U13") (pin "B3") (pinfunction "P0.11/TRACEDATA[0]_B3") (pintype "bidirectional"))
    )
    (net (code "47") (name "/SYS_RST") (class "Default")
      (node (ref "NC12") (pin "2") (pinfunction "2_2") (pintype "passive"))
    )
    (net (code "48") (name "/TX0") (class "Default")
      (node (ref "Q12") (pin "2") (pinfunction "G1_2") (pintype "passive"))
      (node (ref "TP23") (pin "1") (pintype "passive"))
      (node (ref "U13") (pin "G3") (pinfunction "P0.25/AIN4_G3") (pintype "bidirectional"))
      (node (ref "U9") (pin "13") (pinfunction "B2_13") (pintype "bidirectional"))
    )
    (net (code "49") (name "/TX4") (class "Default")
      (node (ref "U13") (pin "G4") (pinfunction "P1.04_G4") (pintype "bidirectional"))
    )
    (net (code "50") (name "/TX5") (class "Default")
      (node (ref "U13") (pin "G9") (pinfunction "P1.13_G9") (pintype "bidirectional"))
    )
    (net (code "51") (name "/TX6") (class "Default")
      (node (ref "U13") (pin "J9") (pinfunction "P0.31_J9") (pintype "bidirectional"))
    )
    (net (code "52") (name "/USB_DNR3_n") (class "Default")
      (node (ref "U13") (pin "D9") (pinfunction "D-_D9") (pintype "bidirectional"))
    )
    (net (code "53") (name "/USB_DNR3_p") (class "Default")
      (node (ref "U13") (pin "C9") (pinfunction "D+_C9") (pintype "bidirectional"))
    )
    (net (code "54") (name "/XL1") (class "Default")
      (node (ref "U13") (pin "C6") (pinfunction "P0.00/XL1_C6") (pintype "bidirectional"))
      (node (ref "X1") (pin "1") (pintype "passive"))
    )
    (net (code "55") (name "/XL2") (class "Default")
      (node (ref "U13") (pin "B6") (pinfunction "P0.01/XL2_B6") (pintype "bidirectional"))
      (node (ref "X1") (pin "2") (pintype "passive"))
    )
    (net (code "56") (name "/nQSPI_CS") (class "Default")
      (node (ref "U13") (pin "E1") (pinfunction "P0.18/QSPI_CS_E1") (pintype "bidirectional"))
      (node (ref "U7") (pin "1") (pinfunction "CS#_1") (pintype "input"))
    )
    (net (code "57") (name "/nRESET") (class "Default")
      (node (ref "D27") (pin "1") (pintype "passive"))
      (node (ref "J11") (pin "10") (pinfunction "nRESET_10") (pintype "passive"))
      (node (ref "J15") (pin "3") (pintype "passive"))
      (node (ref "J17") (pin "3") (pintype "passive"))
      (node (ref "Q25") (pin "6") (pinfunction "D1_6") (pintype "passive"))
      (node (ref "TP47") (pin "1") (pintype "passive"))
      (node (ref "U13") (pin "J3") (pinfunction "~{RESET}_J3") (pintype "input"))
    )
    (net (code "58") (name "/nSARA_PWR_ON") (class "Default")
      (node (ref "U13") (pin "C2") (pinfunction "P0.09/TRACEDATA[2]_C2") (pintype "bidirectional"))
    )
    (net (code "63") (name "3V3") (class "Default")
      (node (ref "C131") (pin "2") (pinfunction "2_2") (pintype "passive"))
      (node (ref "C137") (pin "2") (pinfunction "2_2") (pintype "passive"))
      (node (ref "C39") (pin "2") (pinfunction "2_2") (pintype "passive"))
      (node (ref "C48") (pin "2") (pinfunction "2_2") (pintype "passive"))
      (node (ref "C82") (pin "1") (pinfunction "1_1") (pintype "passive"))
      (node (ref "J11") (pin "1") (pinfunction "VCC_1") (pintype "passive"))
      (node (ref "J15") (pin "1") (pintype "passive"))
      (node (ref "J17") (pin "1") (pintype "passive"))
      (node (ref "J4") (pin "3") (pinfunction "3_3") (pintype "passive"))
      (node (ref "NC9") (pin "2") (pinfunction "2_2") (pintype "passive"))
      (node (ref "Q12") (pin "1") (pinfunction "S1_1") (pintype "passive"))
      (node (ref "Q12") (pin "4") (pinfunction "S2_4") (pintype "passive"))
      (node (ref "R122") (pin "2") (pinfunction "2_2") (pintype "passive"))
      (node (ref "R123") (pin "2") (pinfunction "2_2") (pintype "passive"))
      (node (ref "RGB2") (pin "4") (pinfunction "A_4") (pintype "passive"))
      (node (ref "U7") (pin "8") (pinfunction "VCC_8") (pintype "power_in"))
      (node (ref "U9") (pin "16") (pinfunction "VCCB_16") (pintype "power_in"))
    )
    (net (code "64") (name "3V3_SER") (class "Default")
      (node (ref "C46") (pin "1") (pinfunction "1_1") (pintype "passive"))
      (node (ref "U9") (pin "1") (pinfunction "VCCA_1") (pintype "power_in"))
      (node (ref "U9") (pin "10") (pinfunction "DIR3_10") (pintype "input"))
      (node (ref "U9") (pin "2") (pinfunction "DIR1_2") (pintype "input"))
    )
    (net (code "65") (name "GND") (class "Default")
      (node (ref "BTN1") (pin "3") (pinfunction "3_3") (pintype "passive"))
      (node (ref "BTN1") (pin "4") (pinfunction "4_4") (pintype "passive"))
      (node (ref "BTN2") (pin "3") (pinfunction "3_3") (pintype "passive"))
      (node (ref "BTN2") (pin "4") (pinfunction "4_4") (pintype "passive"))
      (node (ref "C131") (pin "1") (pinfunction "1_1") (pintype "passive"))
      (node (ref "C133") (pin "2") (pinfunction "2_2") (pintype "passive"))
      (node (ref "C134") (pin "1") (pinfunction "1_1") (pintype "passive"))
      (node (ref "C137") (pin "1") (pinfunction "1_1") (pintype "passive"))
      (node (ref "C39") (pin "1") (pinfunction "1_1") (pintype "passive"))
      (node (ref "C46") (pin "2") (pinfunction "2_2") (pintype "passive"))
      (node (ref "C48") (pin "1") (pinfunction "1_1") (pintype "passive"))
      (node (ref "C69") (pin "1") (pinfunction "1_1") (pintype "passive"))
      (node (ref "C70") (pin "1") (pinfunction "1_1") (pintype "passive"))
      (node (ref "C76") (pin "1") (pinfunction "1_1") (pintype "passive"))
      (node (ref "C82") (pin "2") (pinfunction "2_2") (pintype "passive"))
      (node (ref "C86") (pin "2") (pinfunction "2_2") (pintype "passive"))
      (node (ref "D13") (pin "C") (pinfunction "Cathode_C") (pintype "passive"))
      (node (ref "D14") (pin "C") (pinfunction "Cathode_C") (pintype "passive"))
      (node (ref "D22") (pin "2") (pintype "passive"))
      (node (ref "D23") (pin "2") (pintype "passive"))
      (node (ref "D24") (pin "2") (pintype "passive"))
      (node (ref "D25") (pin "2") (pintype "passive"))
      (node (ref "D26") (pin "2") (pintype "passive"))
      (node (ref "D27") (pin "2") (pintype "passive"))
      (node (ref "J11") (pin "3") (pinfunction "GND_3") (pintype "passive"))
      (node (ref "J11") (pin "5") (pinfunction "GND_5") (pintype "passive"))
      (node (ref "J11") (pin "9") (pinfunction "GND_9") (pintype "passive"))
      (node (ref "J15") (pin "5") (pintype "passive"))
      (node (ref "J17") (pin "5") (pintype "passive"))
      (node (ref "J4") (pin "1") (pinfunction "1_1") (pintype "passive"))
      (node (ref "Q16") (pin "1") (pinfunction "S1_1") (pintype "passive"))
      (node (ref "Q16") (pin "4") (pinfunction "S2_4") (pintype "passive"))
      (node (ref "Q16") (pin "5") (pinfunction "G2_5") (pintype "passive"))
      (node (ref "Q17") (pin "1") (pinfunction "S1_1") (pintype "passive"))
      (node (ref "Q17") (pin "4") (pinfunction "S2_4") (pintype "passive"))
      (node (ref "Q18") (pin "1") (pinfunction "S1_1") (pintype "passive"))
      (node (ref "Q25") (pin "1") (pinfunction "S1_1") (pintype "passive"))
      (node (ref "R60") (pin "1") (pinfunction "1_1") (pintype "passive"))
      (node (ref "R61") (pin "1") (pinfunction "1_1") (pintype "passive"))
      (node (ref "R65") (pin "1") (pinfunction "1_1") (pintype "passive"))
      (node (ref "R79") (pin "1") (pinfunction "1_1") (pintype "passive"))
      (node (ref "U13") (pin "A1") (pinfunction "VSS_A1") (pintype "power_in"))
      (node (ref "U13") (pin "A9") (pinfunction "VSS_A9") (pintype "power_in"))
      (node (ref "U13") (pin "B2") (pinfunction "VSS_B2") (pintype "power_in"))
      (node (ref "U13") (pin "B8") (pinfunction "VSS_B8") (pintype "power_in"))
      (node (ref "U13") (pin "E4") (pinfunction "VSS_E4") (pintype "power_in"))
      (node (ref "U13") (pin "E5") (pinfunction "VSS_E5") (pintype "power_in"))
      (node (ref "U13") (pin "F4") (pinfunction "VSS_F4") (pintype "power_in"))
      (node (ref "U13") (pin "F5") (pinfunction "VSS_F5") (pintype "power_in"))
      (node (ref "U13") (pin "K2") (pinfunction "VSS_K2") (pintype "power_in"))
      (node (ref "U13") (pin "K3") (pinfunction "VSS_K3") (pintype "power_in"))
      (node (ref "U13") (pin "K5") (pinfunction "VSS_K5") (pintype "power_in"))
      (node (ref "U13") (pin "K7") (pinfunction "VSS_K7") (pintype "power_in"))
      (node (ref "U13") (pin "K8") (pinfunction "VSS_K8") (pintype "power_in"))
      (node (ref "U13") (pin "L1") (pinfunction "VSS_L1") (pintype "power_in"))
      (node (ref "U13") (pin "L9") (pinfunction "VSS_L9") (pintype "power_in"))
      (node (ref "U13") (pin "M1") (pinfunction "VSS_M1") (pintype "power_in"))
      (node (ref "U13") (pin "M2") (pinfunction "VSS_M2") (pintype "power_in"))
      (node (ref "U13") (pin "M8") (pinfunction "VSS_M8") (pintype "power_in"))
      (node (ref "U13") (pin "M9") (pinfunction "VSS_M9") (pintype "power_in"))
      (node (ref "U7") (pin "4") (pinfunction "GND_4") (pintype "power_in"))
      (node (ref "U9") (pin "15") (pinfunction "DIR2_15") (pintype "input"))
      (node (ref "U9") (pin "7") (pinfunction "DIR4_7") (pintype "input"))
      (node (ref "U9") (pin "8") (pinfunction "GND_8") (pintype "power_in"))
      (node (ref "U9") (pin "9") (pinfunction "~{OE}_9") (pintype "input"))
    )
    (net (code "66") (name "Net-(D13-Anode)") (class "Default")
      (node (ref "D13") (pin "A") (pinfunction "Anode_A") (pintype "passive"))
      (node (ref "R38") (pin "1") (pinfunction "1_1") (pintype "passive"))
    )
    (net (code "67") (name "Net-(D14-Anode)") (class "Default")
      (node (ref "D14") (pin "A") (pinfunction "Anode_A") (pintype "passive"))
      (node (ref "R39") (pin "1") (pinfunction "1_1") (pintype "passive"))
    )
    (net (code "68") (name "Net-(Q12A-D1)") (class "Default")
      (node (ref "Q12") (pin "6") (pinfunction "D1_6") (pintype "passive"))
      (node (ref "R38") (pin "2") (pinfunction "2_2") (pintype "passive"))
    )
    (net (code "69") (name "Net-(Q12B-D2)") (class "Default")
      (node (ref "Q12") (pin "3") (pinfunction "D2_3") (pintype "passive"))
      (node (ref "R39") (pin "2") (pinfunction "2_2") (pintype "passive"))
    )
    (net (code "70") (name "Net-(Q16A-D1)") (class "Default")
      (node (ref "Q16") (pin "6") (pinfunction "D1_6") (pintype "passive"))
      (node (ref "R62") (pin "1") (pinfunction "1_1") (pintype "passive"))
    )
    (net (code "71") (name "Net-(Q17A-D1)") (class "Default")
      (node (ref "Q17") (pin "6") (pinfunction "D1_6") (pintype "passive"))
      (node (ref "R66") (pin "1") (pinfunction "1_1") (pintype "passive"))
    )
    (net (code "72") (name "Net-(Q17B-D2)") (class "Default")
      (node (ref "Q17") (pin "3") (pinfunction "D2_3") (pintype "passive"))
      (node (ref "R64") (pin "1") (pinfunction "1_1") (pintype "passive"))
    )
    (net (code "73") (name "Net-(Q18A-D1)") (class "Default")
      (node (ref "Q18") (pin "5") (pinfunction "G2_5") (pintype "passive"))
      (node (ref "Q18") (pin "6") (pinfunction "D1_6") (pintype "passive"))
      (node (ref "R80") (pin "2") (pinfunction "2_2") (pintype "passive"))
    )
    (net (code "74") (name "Net-(Q18B-D2)") (class "Default")
      (node (ref "C76") (pin "2") (pinfunction "2_2") (pintype "passive"))
      (node (ref "Q18") (pin "3") (pinfunction "D2_3") (pintype "passive"))
      (node (ref "U13") (pin "B9") (pinfunction "VBUS_B9") (pintype "power_in"))
    )
    (net (code "75") (name "Net-(Q25A-G1)") (class "Default")
      (node (ref "NC12") (pin "1") (pinfunction "1_1") (pintype "passive"))
      (node (ref "Q25") (pin "2") (pinfunction "G1_2") (pintype "passive"))
    )
    (net (code "76") (name "Net-(RGB2-B)") (class "Default")
      (node (ref "R66") (pin "2") (pinfunction "2_2") (pintype "passive"))
      (node (ref "RGB2") (pin "3") (pinfunction "B_3") (pintype "passive"))
    )
    (net (code "77") (name "Net-(RGB2-G)") (class "Default")
      (node (ref "R64") (pin "2") (pinfunction "2_2") (pintype "passive"))
      (node (ref "RGB2") (pin "2") (pinfunction "G_2") (pintype "passive"))
    )
    (net (code "78") (name "Net-(RGB2-R)") (class "Default")
      (node (ref "R62") (pin "2") (pinfunction "2_2") (pintype "passive"))
      (node (ref "RGB2") (pin "1") (pinfunction "R_1") (pintype "passive"))
    )
    (net (code "79") (name "VBUS") (class "Default")
      (node (ref "Q18") (pin "4") (pinfunction "S2_4") (pintype "passive"))
      (node (ref "R80") (pin "1") (pinfunction "1_1") (pintype "passive"))
    )
    (net (code "80") (name "VDD_NORA") (class "Default")
      (node (ref "C69") (pin "2") (pinfunction "2_2") (pintype "passive"))
      (node (ref "C70") (pin "2") (pinfunction "2_2") (pintype "passive"))
      (node (ref "C86") (pin "1") (pinfunction "1_1") (pintype "passive"))
      (node (ref "J4") (pin "2") (pinfunction "2_2") (pintype "passive"))
      (node (ref "NC9") (pin "1") (pinfunction "1_1") (pintype "passive"))
      (node (ref "Q18") (pin "2") (pinfunction "G1_2") (pintype "passive"))
      (node (ref "R79") (pin "2") (pinfunction "2_2") (pintype "passive"))
      (node (ref "TP36") (pin "1") (pintype "passive"))
      (node (ref "U13") (pin "A7") (pinfunction "VDD_A7") (pintype "power_in"))
      (node (ref "U13") (pin "A8") (pinfunction "VDDH_A8") (pintype "power_in"))
      (node (ref "U13") (pin "B7") (pinfunction "VDD_B7") (pintype "power_in"))
    )
    (net (code "81") (name "unconnected-(J11-KEY-Pad7)") (class "Default")
      (node (ref "J11") (pin "7") (pinfunction "KEY_7") (pintype "passive+no_connect"))
    )
    (net (code "82") (name "unconnected-(J11-TDI-Pad8)") (class "Default")
      (node (ref "J11") (pin "8") (pinfunction "TDI_8") (pintype "passive+no_connect"))
    )
    (net (code "83") (name "unconnected-(J13-Pad1)") (class "Default")
      (node (ref "J13") (pin "1") (pinfunction "1_1") (pintype "passive+no_connect"))
    )
    (net (code "84") (name "unconnected-(J13-Pad3)") (class "Default")
      (node (ref "J13") (pin "3") (pinfunction "3_3") (pintype "passive+no_connect"))
    )
    (net (code "85") (name "unconnected-(J13-Pad5)") (class "Default")
      (node (ref "J13") (pin "5") (pinfunction "5_5") (pintype "passive+no_connect"))
    )
    (net (code "86") (name "unconnected-(Q16B-D2-Pad3)") (class "Default")
      (node (ref "Q16") (pin "3") (pinfunction "D2_3") (pintype "passive+no_connect"))
    )
    (net (code "87") (name "unconnected-(U9-A1-Pad3)") (class "Default")
      (node (ref "U9") (pin "3") (pinfunction "A1_3") (pintype "bidirectional"))
    )
    (net (code "88") (name "unconnected-(U9-A2-Pad4)") (class "Default")
      (node (ref "U9") (pin "4") (pinfunction "A2_4") (pintype "bidirectional"))
    )
    (net (code "89") (name "unconnected-(U9-A3-Pad5)") (class "Default")
      (node (ref "U9") (pin "5") (pinfunction "A3_5") (pintype "bidirectional"))
    )
    (net (code "90") (name "unconnected-(U9-A4-Pad6)") (class "Default")
      (node (ref "U9") (pin "6") (pinfunction "A4_6") (pintype "bidirectional"))
    )
    (net (code "91") (name "unconnected-(U13A-N.C.-PadA6)") (class "Default")
      (node (ref "U13") (pin "A6") (pinfunction "N.C._A6") (pintype "tri_state+no_connect"))
    )
    (net (code "92") (name "unconnected-(U13A-N.C.-PadJ1)") (class "Default")
      (node (ref "U13") (pin "J1") (pinfunction "N.C._J1") (pintype "tri_state+no_connect"))
    )
    (net (code "93") (name "unconnected-(U13A-N.C.-PadJ4)") (class "Default")
      (node (ref "U13") (pin "J4") (pinfunction "N.C._J4") (pintype "tri_state+no_connect"))
    )
    (net (code "94") (name "unconnected-(U13A-N.C.-PadJ5)") (class "Default")
      (node (ref "U13") (pin "J5") (pinfunction "N.C._J5") (pintype "tri_state+no_connect"))
    )
    (net (code "95") (name "unconnected-(U13A-N.C.-PadK1)") (class "Default")
      (node (ref "U13") (pin "K1") (pinfunction "N.C._K1") (pintype "tri_state+no_connect"))
    )
    (net (code "96") (name "unconnected-(U13A-N.C.-PadK9)") (class "Default")
      (node (ref "U13") (pin "K9") (pinfunction "N.C._K9") (pintype "tri_state+no_connect"))
    )
  )
)
